# USB.net
KiCad netlist of a schematic drawn in Altium Designer
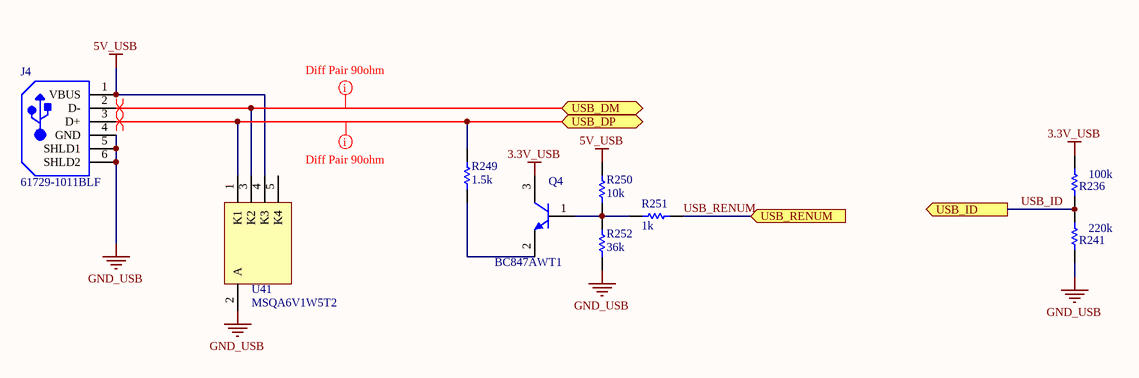
[diagram p0: USB.SchDoc]

(export (version "E")
  (design (tool "Eeschema 10.0.6"))
  (components
    (comp (ref "J4")
      (value "61729-1011BLF")
      (footprint "FCI-61729-1011BLF_V")
      (description "USB Receptacle B Type, Right Angle, -40 to 85 degC, 4-Pin THD, RoHS, Tube")
      (fields (field (name "TOLERANCE") "20%"))
      (libsource (lib "Altium Content Vault") (part "USB-4-2SHLD"))
    )
    (comp (ref "Q4")
      (value "BC847AWT1")
      (footprint "ONSC-SC-70-3-419-04_V")
      (description "General Purpose Transistor, NPN Silicon, 3-Pin SC70, Tape and Reel")
      (fields (field (name "MANUFACTURER") "On Semiconductor"))
      (libsource (lib "Altium Content Vault") (part "ONSC-NPN-B1E2C3-3"))
    )
    (comp (ref "R236")
      (value "100k")
      (footprint "RESC0402(1005)_L")
      (description "0402 (1005 Metric) Chip Resistor")
      (fields (field (name "Comment") "RES0402"))
      (libsource (lib "Altium Content Vault") (part "CMP-1591-00004-1"))
    )
    (comp (ref "R241")
      (value "220k")
      (footprint "RESC0402(1005)_L")
      (description "0402 (1005 Metric) Chip Resistor")
      (fields (field (name "Comment") "RES0402"))
      (libsource (lib "Altium Content Vault") (part "CMP-1591-00004-1"))
    )
    (comp (ref "R249")
      (value "1.5k")
      (footprint "RESC0402(1005)_L")
      (description "0402 (1005 Metric) Chip Resistor")
      (fields (field (name "Comment") "RES0402"))
      (libsource (lib "Altium Content Vault") (part "CMP-1591-00004-1"))
    )
    (comp (ref "R250")
      (value "10k")
      (footprint "RESC0402(1005)_L")
      (description "0402 (1005 Metric) Chip Resistor")
      (fields (field (name "Comment") "RES0402"))
      (libsource (lib "Altium Content Vault") (part "CMP-1591-00004-1"))
    )
    (comp (ref "R251")
      (value "1k")
      (footprint "RESC0402(1005)_L")
      (description "0402 (1005 Metric) Chip Resistor")
      (fields (field (name "Comment") "RES0402"))
      (libsource (lib "Altium Content Vault") (part "CMP-1591-00004-1"))
    )
    (comp (ref "R252")
      (value "36k")
      (footprint "RESC0402(1005)_L")
      (description "0402 (1005 Metric) Chip Resistor")
      (fields (field (name "Comment") "RES0402"))
      (libsource (lib "Altium Content Vault") (part "CMP-1591-00004-1"))
    )
    (comp (ref "U41")
      (value "MSQA6V1W5T2")
      (footprint "ONSC-SC70-5-419A-02_V")
      (description "Quad Array ESD Protection Diodes with Low Clamping Voltage, 5-Pin SC70, Tape and Reel")
      (fields (field (name "MANUFACTURER") "On Semiconductor"))
      (libsource (lib "Altium Content Vault") (part "ONSC-MSQA6V1W5-SC70-5-419A-02"))
    )
  )
  (nets
    (net (code "1") (name "/USB_DM") (class "Default")
      (node (ref "J4") (pin "2") (pinfunction "D-_2") (pintype "passive"))
      (node (ref "U41") (pin "3") (pinfunction "K2_3") (pintype "passive"))
    )
    (net (code "2") (name "/USB_DP") (class "Default")
      (node (ref "J4") (pin "3") (pinfunction "D+_3") (pintype "passive"))
      (node (ref "R249") (pin "1") (pinfunction "1_1") (pintype "passive"))
      (node (ref "U41") (pin "1") (pinfunction "K1_1") (pintype "passive"))
    )
    (net (code "3") (name "/USB_ID") (class "Default")
      (node (ref "R236") (pin "1") (pinfunction "1_1") (pintype "passive"))
      (node (ref "R241") (pin "2") (pinfunction "2_2") (pintype "passive"))
    )
    (net (code "4") (name "/USB_RENUM") (class "Default")
      (node (ref "R251") (pin "2") (pinfunction "2_2") (pintype "passive"))
    )
    (net (code "5") (name "3.3V_USB") (class "Default")
      (node (ref "Q4") (pin "3") (pinfunction "C_3") (pintype "passive"))
      (node (ref "R236") (pin "2") (pinfunction "2_2") (pintype "passive"))
    )
    (net (code "6") (name "5V_USB") (class "Default")
      (node (ref "J4") (pin "1") (pinfunction "VBUS_1") (pintype "passive"))
      (node (ref "R250") (pin "1") (pinfunction "1_1") (pintype "passive"))
      (node (ref "U41") (pin "4") (pinfunction "K3_4") (pintype "passive"))
    )
    (net (code "7") (name "GND_USB") (class "Default")
      (node (ref "J4") (pin "4") (pinfunction "GND_4") (pintype "passive"))
      (node (ref "J4") (pin "5") (pinfunction "SHLD1_5") (pintype "passive"))
      (node (ref "J4") (pin "6") (pinfunction "SHLD2_6") (pintype "passive"))
      (node (ref "R241") (pin "1") (pinfunction "1_1") (pintype "passive"))
      (node (ref "R252") (pin "2") (pinfunction "2_2") (pintype "passive"))
      (node (ref "U41") (pin "2") (pinfunction "A_2") (pintype "passive"))
    )
    (net (code "8") (name "Net-(Q4-B)") (class "Default")
      (node (ref "Q4") (pin "1") (pinfunction "B_1") (pintype "passive"))
      (node (ref "R250") (pin "2") (pinfunction "2_2") (pintype "passive"))
      (node (ref "R251") (pin "1") (pinfunction "1_1") (pintype "passive"))
      (node (ref "R252") (pin "1") (pinfunction "1_1") (pintype "passive"))
    )
    (net (code "9") (name "Net-(Q4-E)") (class "Default")
      (node (ref "Q4") (pin "2") (pinfunction "E_2") (pintype "passive"))
      (node (ref "R249") (pin "2") (pinfunction "2_2") (pintype "passive"))
    )
    (net (code "10") (name "unconnected-(U41-K4-Pad5)") (class "Default")
      (node (ref "U41") (pin "5") (pinfunction "K4_5") (pintype "passive"))
    )
  )
)
